# Display.net
KiCad netlist of a schematic drawn in Altium Designer
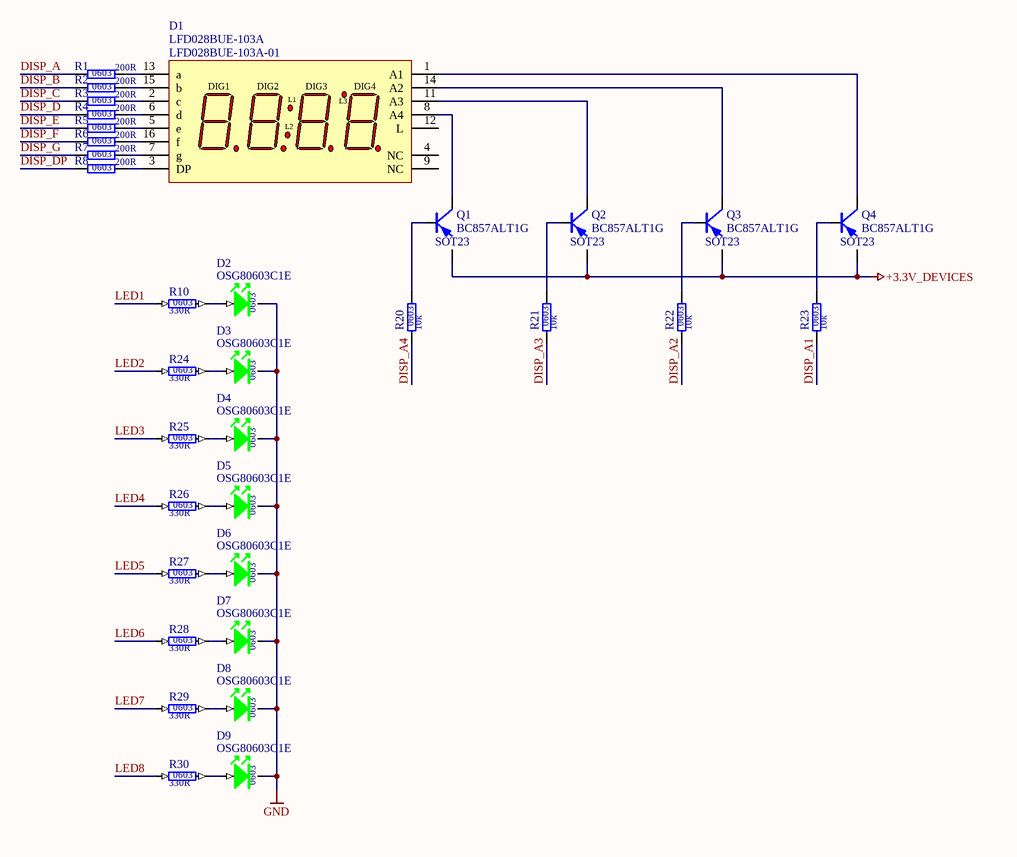
[diagram p0: Display.SchDoc]

(export (version "E")
  (design (tool "Eeschema 10.0.6"))
  (components
    (comp (ref "D1")
      (value "LFD028BUE-103A-01")
      (footprint "LFD028BUE-103A-01")
      (fields
        (field (name "SCH_FOOTPRINT") "LFD028BUE-103A")
        (field (name "PART NUMBER") "OL_LFD028BUE-103A-01")
        (field (name "MANUFACTURER") "WENRUN")
        (field (name "Comment") "4x7 SEG 0.28'")
      )
      (libsource (lib "Library") (part "OL_LFD028BUE-103A"))
    )
    (comp (ref "D2")
      (value "OSG80603C1E")
      (footprint "OL_0603_1608")
      (description "LED GREEN")
      (fields
        (field (name "SCH_FOOTPRINT") "0603")
        (field (name "PART NUMBER") "OL_G_0603_OSG80603C1E")
        (field (name "MANUFACTURER") "Optosupply")
      )
      (libsource (lib "Library") (part "OL_G"))
    )
    (comp (ref "D3")
      (value "OSG80603C1E")
      (footprint "OL_0603_1608")
      (description "LED GREEN")
      (fields
        (field (name "SCH_FOOTPRINT") "0603")
        (field (name "PART NUMBER") "OL_G_0603_OSG80603C1E")
        (field (name "MANUFACTURER") "Optosupply")
      )
      (libsource (lib "Library") (part "OL_G"))
    )
    (comp (ref "D4")
      (value "OSG80603C1E")
      (footprint "OL_0603_1608")
      (description "LED GREEN")
      (fields
        (field (name "SCH_FOOTPRINT") "0603")
        (field (name "PART NUMBER") "OL_G_0603_OSG80603C1E")
        (field (name "MANUFACTURER") "Optosupply")
      )
      (libsource (lib "Library") (part "OL_G"))
    )
    (comp (ref "D5")
      (value "OSG80603C1E")
      (footprint "OL_0603_1608")
      (description "LED GREEN")
      (fields
        (field (name "SCH_FOOTPRINT") "0603")
        (field (name "PART NUMBER") "OL_G_0603_OSG80603C1E")
        (field (name "MANUFACTURER") "Optosupply")
      )
      (libsource (lib "Library") (part "OL_G"))
    )
    (comp (ref "D6")
      (value "OSG80603C1E")
      (footprint "OL_0603_1608")
      (description "LED GREEN")
      (fields
        (field (name "SCH_FOOTPRINT") "0603")
        (field (name "PART NUMBER") "OL_G_0603_OSG80603C1E")
        (field (name "MANUFACTURER") "Optosupply")
      )
      (libsource (lib "Library") (part "OL_G"))
    )
    (comp (ref "D7")
      (value "OSG80603C1E")
      (footprint "OL_0603_1608")
      (description "LED GREEN")
      (fields
        (field (name "SCH_FOOTPRINT") "0603")
        (field (name "PART NUMBER") "OL_G_0603_OSG80603C1E")
        (field (name "MANUFACTURER") "Optosupply")
      )
      (libsource (lib "Library") (part "OL_G"))
    )
    (comp (ref "D8")
      (value "OSG80603C1E")
      (footprint "OL_0603_1608")
      (description "LED GREEN")
      (fields
        (field (name "SCH_FOOTPRINT") "0603")
        (field (name "PART NUMBER") "OL_G_0603_OSG80603C1E")
        (field (name "MANUFACTURER") "Optosupply")
      )
      (libsource (lib "Library") (part "OL_G"))
    )
    (comp (ref "D9")
      (value "OSG80603C1E")
      (footprint "OL_0603_1608")
      (description "LED GREEN")
      (fields
        (field (name "SCH_FOOTPRINT") "0603")
        (field (name "PART NUMBER") "OL_G_0603_OSG80603C1E")
        (field (name "MANUFACTURER") "Optosupply")
      )
      (libsource (lib "Library") (part "OL_G"))
    )
    (comp (ref "Q1")
      (value "BC857ALT1G")
      (footprint "SOT23_TO236_SC59")
      (description "Transitor PNP")
      (fields
        (field (name "SCH_FOOTPRINT") "SOT23")
        (field (name "PART NUMBER") "QPN_BC857ALT1G")
        (field (name "VOLTAGE") "45V")
      )
      (libsource (lib "Library") (part "QPN_BEC"))
    )
    (comp (ref "Q2")
      (value "BC857ALT1G")
      (footprint "SOT23_TO236_SC59")
      (description "Transitor PNP")
      (fields
        (field (name "SCH_FOOTPRINT") "SOT23")
        (field (name "PART NUMBER") "QPN_BC857ALT1G")
        (field (name "VOLTAGE") "45V")
      )
      (libsource (lib "Library") (part "QPN_BEC"))
    )
    (comp (ref "Q3")
      (value "BC857ALT1G")
      (footprint "SOT23_TO236_SC59")
      (description "Transitor PNP")
      (fields
        (field (name "SCH_FOOTPRINT") "SOT23")
        (field (name "PART NUMBER") "QPN_BC857ALT1G")
        (field (name "VOLTAGE") "45V")
      )
      (libsource (lib "Library") (part "QPN_BEC"))
    )
    (comp (ref "Q4")
      (value "BC857ALT1G")
      (footprint "SOT23_TO236_SC59")
      (description "Transitor PNP")
      (fields
        (field (name "SCH_FOOTPRINT") "SOT23")
        (field (name "PART NUMBER") "QPN_BC857ALT1G")
        (field (name "VOLTAGE") "45V")
      )
      (libsource (lib "Library") (part "QPN_BEC"))
    )
    (comp (ref "R1")
      (value "200R")
      (footprint "R_0603_1608")
      (fields
        (field (name "SCH_FOOTPRINT") "0603")
        (field (name "PART NUMBER") "R_200R_0603_1")
        (field (name "VOLTAGE") "50V")
        (field (name "POWER") "100mW")
      )
      (libsource (lib "") (part "R_1"))
    )
    (comp (ref "R2")
      (value "200R")
      (footprint "R_0603_1608")
      (fields
        (field (name "SCH_FOOTPRINT") "0603")
        (field (name "PART NUMBER") "R_200R_0603_1")
        (field (name "VOLTAGE") "50V")
        (field (name "POWER") "100mW")
      )
      (libsource (lib "") (part "R_1"))
    )
    (comp (ref "R3")
      (value "200R")
      (footprint "R_0603_1608")
      (fields
        (field (name "SCH_FOOTPRINT") "0603")
        (field (name "PART NUMBER") "R_200R_0603_1")
        (field (name "VOLTAGE") "50V")
        (field (name "POWER") "100mW")
      )
      (libsource (lib "") (part "R_1"))
    )
    (comp (ref "R4")
      (value "200R")
      (footprint "R_0603_1608")
      (fields
        (field (name "SCH_FOOTPRINT") "0603")
        (field (name "PART NUMBER") "R_200R_0603_1")
        (field (name "VOLTAGE") "50V")
        (field (name "POWER") "100mW")
      )
      (libsource (lib "") (part "R_1"))
    )
    (comp (ref "R5")
      (value "200R")
      (footprint "R_0603_1608")
      (fields
        (field (name "SCH_FOOTPRINT") "0603")
        (field (name "PART NUMBER") "R_200R_0603_1")
        (field (name "VOLTAGE") "50V")
        (field (name "POWER") "100mW")
      )
      (libsource (lib "") (part "R_1"))
    )
    (comp (ref "R6")
      (value "200R")
      (footprint "R_0603_1608")
      (fields
        (field (name "SCH_FOOTPRINT") "0603")
        (field (name "PART NUMBER") "R_200R_0603_1")
        (field (name "VOLTAGE") "50V")
        (field (name "POWER") "100mW")
      )
      (libsource (lib "") (part "R_1"))
    )
    (comp (ref "R7")
      (value "200R")
      (footprint "R_0603_1608")
      (fields
        (field (name "SCH_FOOTPRINT") "0603")
        (field (name "PART NUMBER") "R_200R_0603_1")
        (field (name "VOLTAGE") "50V")
        (field (name "POWER") "100mW")
      )
      (libsource (lib "") (part "R_1"))
    )
    (comp (ref "R8")
      (value "200R")
      (footprint "R_0603_1608")
      (fields
        (field (name "SCH_FOOTPRINT") "0603")
        (field (name "PART NUMBER") "R_200R_0603_1")
        (field (name "VOLTAGE") "50V")
        (field (name "POWER") "100mW")
      )
      (libsource (lib "") (part "R_1"))
    )
    (comp (ref "R10")
      (value "330R")
      (footprint "R_0603_1608")
      (fields
        (field (name "SCH_FOOTPRINT") "0603")
        (field (name "PART NUMBER") "R_330R_0603_1")
        (field (name "VOLTAGE") "50V")
        (field (name "POWER") "100mW")
      )
      (libsource (lib "Library") (part "R"))
    )
    (comp (ref "R20")
      (value "10k")
      (footprint "R_0603_1608")
      (fields
        (field (name "SCH_FOOTPRINT") "0603")
        (field (name "PART NUMBER") "R_10k_0603_1")
        (field (name "VOLTAGE") "75V")
        (field (name "POWER") "100mW")
      )
      (libsource (lib "") (part "R_1"))
    )
    (comp (ref "R21")
      (value "10k")
      (footprint "R_0603_1608")
      (fields
        (field (name "SCH_FOOTPRINT") "0603")
        (field (name "PART NUMBER") "R_10k_0603_1")
        (field (name "VOLTAGE") "75V")
        (field (name "POWER") "100mW")
      )
      (libsource (lib "") (part "R_1"))
    )
    (comp (ref "R22")
      (value "10k")
      (footprint "R_0603_1608")
      (fields
        (field (name "SCH_FOOTPRINT") "0603")
        (field (name "PART NUMBER") "R_10k_0603_1")
        (field (name "VOLTAGE") "75V")
        (field (name "POWER") "100mW")
      )
      (libsource (lib "") (part "R_1"))
    )
    (comp (ref "R23")
      (value "10k")
      (footprint "R_0603_1608")
      (fields
        (field (name "SCH_FOOTPRINT") "0603")
        (field (name "PART NUMBER") "R_10k_0603_1")
        (field (name "VOLTAGE") "75V")
        (field (name "POWER") "100mW")
      )
      (libsource (lib "") (part "R_1"))
    )
    (comp (ref "R24")
      (value "330R")
      (footprint "R_0603_1608")
      (fields
        (field (name "SCH_FOOTPRINT") "0603")
        (field (name "PART NUMBER") "R_330R_0603_1")
        (field (name "VOLTAGE") "50V")
        (field (name "POWER") "100mW")
      )
      (libsource (lib "Library") (part "R"))
    )
    (comp (ref "R25")
      (value "330R")
      (footprint "R_0603_1608")
      (fields
        (field (name "SCH_FOOTPRINT") "0603")
        (field (name "PART NUMBER") "R_330R_0603_1")
        (field (name "VOLTAGE") "50V")
        (field (name "POWER") "100mW")
      )
      (libsource (lib "Library") (part "R"))
    )
    (comp (ref "R26")
      (value "330R")
      (footprint "R_0603_1608")
      (fields
        (field (name "SCH_FOOTPRINT") "0603")
        (field (name "PART NUMBER") "R_330R_0603_1")
        (field (name "VOLTAGE") "50V")
        (field (name "POWER") "100mW")
      )
      (libsource (lib "Library") (part "R"))
    )
    (comp (ref "R27")
      (value "330R")
      (footprint "R_0603_1608")
      (fields
        (field (name "SCH_FOOTPRINT") "0603")
        (field (name "PART NUMBER") "R_330R_0603_1")
        (field (name "VOLTAGE") "50V")
        (field (name "POWER") "100mW")
      )
      (libsource (lib "Library") (part "R"))
    )
    (comp (ref "R28")
      (value "330R")
      (footprint "R_0603_1608")
      (fields
        (field (name "SCH_FOOTPRINT") "0603")
        (field (name "PART NUMBER") "R_330R_0603_1")
        (field (name "VOLTAGE") "50V")
        (field (name "POWER") "100mW")
      )
      (libsource (lib "Library") (part "R"))
    )
    (comp (ref "R29")
      (value "330R")
      (footprint "R_0603_1608")
      (fields
        (field (name "SCH_FOOTPRINT") "0603")
        (field (name "PART NUMBER") "R_330R_0603_1")
        (field (name "VOLTAGE") "50V")
        (field (name "POWER") "100mW")
      )
      (libsource (lib "Library") (part "R"))
    )
    (comp (ref "R30")
      (value "330R")
      (footprint "R_0603_1608")
      (fields
        (field (name "SCH_FOOTPRINT") "0603")
        (field (name "PART NUMBER") "R_330R_0603_1")
        (field (name "VOLTAGE") "50V")
        (field (name "POWER") "100mW")
      )
      (libsource (lib "Library") (part "R"))
    )
  )
  (nets
    (net (code "1") (name "+3.3V_DEVICES") (class "Default")
      (node (ref "Q1") (pin "2") (pinfunction "E_2") (pintype "passive"))
      (node (ref "Q2") (pin "2") (pinfunction "E_2") (pintype "passive"))
      (node (ref "Q3") (pin "2") (pinfunction "E_2") (pintype "passive"))
      (node (ref "Q4") (pin "2") (pinfunction "E_2") (pintype "passive"))
    )
    (net (code "2") (name "/DISP_A") (class "Default")
      (node (ref "R1") (pin "1") (pinfunction "1_1") (pintype "passive"))
    )
    (net (code "3") (name "/DISP_A1") (class "Default")
      (node (ref "R23") (pin "1") (pinfunction "1_1") (pintype "passive"))
    )
    (net (code "4") (name "/DISP_A2") (class "Default")
      (node (ref "R22") (pin "1") (pinfunction "1_1") (pintype "passive"))
    )
    (net (code "5") (name "/DISP_A3") (class "Default")
      (node (ref "R21") (pin "1") (pinfunction "1_1") (pintype "passive"))
    )
    (net (code "6") (name "/DISP_A4") (class "Default")
      (node (ref "R20") (pin "1") (pinfunction "1_1") (pintype "passive"))
    )
    (net (code "7") (name "/DISP_B") (class "Default")
      (node (ref "R2") (pin "1") (pinfunction "1_1") (pintype "passive"))
    )
    (net (code "8") (name "/DISP_C") (class "Default")
      (node (ref "R3") (pin "1") (pinfunction "1_1") (pintype "passive"))
    )
    (net (code "9") (name "/DISP_D") (class "Default")
      (node (ref "R4") (pin "1") (pinfunction "1_1") (pintype "passive"))
    )
    (net (code "10") (name "/DISP_DP") (class "Default")
      (node (ref "R8") (pin "1") (pinfunction "1_1") (pintype "passive"))
    )
    (net (code "11") (name "/DISP_E") (class "Default")
      (node (ref "R5") (pin "1") (pinfunction "1_1") (pintype "passive"))
    )
    (net (code "12") (name "/DISP_F") (class "Default")
      (node (ref "R6") (pin "1") (pinfunction "1_1") (pintype "passive"))
    )
    (net (code "13") (name "/DISP_G") (class "Default")
      (node (ref "R7") (pin "1") (pinfunction "1_1") (pintype "passive"))
    )
    (net (code "14") (name "/LED1") (class "Default")
      (node (ref "R10") (pin "1") (pinfunction "1_1") (pintype "input"))
    )
    (net (code "15") (name "/LED2") (class "Default")
      (node (ref "R24") (pin "1") (pinfunction "1_1") (pintype "input"))
    )
    (net (code "16") (name "/LED3") (class "Default")
      (node (ref "R25") (pin "1") (pinfunction "1_1") (pintype "input"))
    )
    (net (code "17") (name "/LED4") (class "Default")
      (node (ref "R26") (pin "1") (pinfunction "1_1") (pintype "input"))
    )
    (net (code "18") (name "/LED5") (class "Default")
      (node (ref "R27") (pin "1") (pinfunction "1_1") (pintype "input"))
    )
    (net (code "19") (name "/LED6") (class "Default")
      (node (ref "R28") (pin "1") (pinfunction "1_1") (pintype "input"))
    )
    (net (code "20") (name "/LED7") (class "Default")
      (node (ref "R29") (pin "1") (pinfunction "1_1") (pintype "input"))
    )
    (net (code "21") (name "/LED8") (class "Default")
      (node (ref "R30") (pin "1") (pinfunction "1_1") (pintype "input"))
    )
    (net (code "22") (name "GND") (class "Default")
      (node (ref "D2") (pin "1") (pinfunction "K_1") (pintype "output"))
      (node (ref "D3") (pin "1") (pinfunction "K_1") (pintype "output"))
      (node (ref "D4") (pin "1") (pinfunction "K_1") (pintype "output"))
      (node (ref "D5") (pin "1") (pinfunction "K_1") (pintype "output"))
      (node (ref "D6") (pin "1") (pinfunction "K_1") (pintype "output"))
      (node (ref "D7") (pin "1") (pinfunction "K_1") (pintype "output"))
      (node (ref "D8") (pin "1") (pinfunction "K_1") (pintype "output"))
      (node (ref "D9") (pin "1") (pinfunction "K_1") (pintype "output"))
    )
    (net (code "23") (name "Net-(D1-A1)") (class "Default")
      (node (ref "D1") (pin "1") (pinfunction "A1_1") (pintype "passive"))
      (node (ref "Q4") (pin "3") (pinfunction "C_3") (pintype "passive"))
    )
    (net (code "24") (name "Net-(D1-A2)") (class "Default")
      (node (ref "D1") (pin "14") (pinfunction "A2_14") (pintype "passive"))
      (node (ref "Q3") (pin "3") (pinfunction "C_3") (pintype "passive"))
    )
    (net (code "25") (name "Net-(D1-A3)") (class "Default")
      (node (ref "D1") (pin "11") (pinfunction "A3_11") (pintype "passive"))
      (node (ref "Q2") (pin "3") (pinfunction "C_3") (pintype "passive"))
    )
    (net (code "26") (name "Net-(D1-A4)") (class "Default")
      (node (ref "D1") (pin "8") (pinfunction "A4_8") (pintype "passive"))
      (node (ref "Q1") (pin "3") (pinfunction "C_3") (pintype "passive"))
    )
    (net (code "27") (name "Net-(D1-DP)") (class "Default")
      (node (ref "D1") (pin "3") (pinfunction "DP_3") (pintype "passive"))
      (node (ref "R8") (pin "2") (pinfunction "2_2") (pintype "passive"))
    )
    (net (code "28") (name "Net-(D1-a)") (class "Default")
      (node (ref "D1") (pin "13") (pinfunction "a_13") (pintype "passive"))
      (node (ref "R1") (pin "2") (pinfunction "2_2") (pintype "passive"))
    )
    (net (code "29") (name "Net-(D1-b)") (class "Default")
      (node (ref "D1") (pin "15") (pinfunction "b_15") (pintype "passive"))
      (node (ref "R2") (pin "2") (pinfunction "2_2") (pintype "passive"))
    )
    (net (code "30") (name "Net-(D1-c)") (class "Default")
      (node (ref "D1") (pin "2") (pinfunction "c_2") (pintype "passive"))
      (node (ref "R3") (pin "2") (pinfunction "2_2") (pintype "passive"))
    )
    (net (code "31") (name "Net-(D1-d)") (class "Default")
      (node (ref "D1") (pin "6") (pinfunction "d_6") (pintype "passive"))
      (node (ref "R4") (pin "2") (pinfunction "2_2") (pintype "passive"))
    )
    (net (code "32") (name "Net-(D1-e)") (class "Default")
      (node (ref "D1") (pin "5") (pinfunction "e_5") (pintype "passive"))
      (node (ref "R5") (pin "2") (pinfunction "2_2") (pintype "passive"))
    )
    (net (code "33") (name "Net-(D1-f)") (class "Default")
      (node (ref "D1") (pin "16") (pinfunction "f_16") (pintype "passive"))
      (node (ref "R6") (pin "2") (pinfunction "2_2") (pintype "passive"))
    )
    (net (code "34") (name "Net-(D1-g)") (class "Default")
      (node (ref "D1") (pin "7") (pinfunction "g_7") (pintype "passive"))
      (node (ref "R7") (pin "2") (pinfunction "2_2") (pintype "passive"))
    )
    (net (code "35") (name "Net-(D2-A)") (class "Default")
      (node (ref "D2") (pin "2") (pinfunction "A_2") (pintype "input"))
      (node (ref "R10") (pin "2") (pinfunction "2_2") (pintype "output"))
    )
    (net (code "36") (name "Net-(D3-A)") (class "Default")
      (node (ref "D3") (pin "2") (pinfunction "A_2") (pintype "input"))
      (node (ref "R24") (pin "2") (pinfunction "2_2") (pintype "output"))
    )
    (net (code "37") (name "Net-(D4-A)") (class "Default")
      (node (ref "D4") (pin "2") (pinfunction "A_2") (pintype "input"))
      (node (ref "R25") (pin "2") (pinfunction "2_2") (pintype "output"))
    )
    (net (code "38") (name "Net-(D5-A)") (class "Default")
      (node (ref "D5") (pin "2") (pinfunction "A_2") (pintype "input"))
      (node (ref "R26") (pin "2") (pinfunction "2_2") (pintype "output"))
    )
    (net (code "39") (name "Net-(D6-A)") (class "Default")
      (node (ref "D6") (pin "2") (pinfunction "A_2") (pintype "input"))
      (node (ref "R27") (pin "2") (pinfunction "2_2") (pintype "output"))
    )
    (net (code "40") (name "Net-(D7-A)") (class "Default")
      (node (ref "D7") (pin "2") (pinfunction "A_2") (pintype "input"))
      (node (ref "R28") (pin "2") (pinfunction "2_2") (pintype "output"))
    )
    (net (code "41") (name "Net-(D8-A)") (class "Default")
      (node (ref "D8") (pin "2") (pinfunction "A_2") (pintype "input"))
      (node (ref "R29") (pin "2") (pinfunction "2_2") (pintype "output"))
    )
    (net (code "42") (name "Net-(D9-A)") (class "Default")
      (node (ref "D9") (pin "2") (pinfunction "A_2") (pintype "input"))
      (node (ref "R30") (pin "2") (pinfunction "2_2") (pintype "output"))
    )
    (net (code "43") (name "Net-(Q1-B)") (class "Default")
      (node (ref "Q1") (pin "1") (pinfunction "B_1") (pintype "passive"))
      (node (ref "R20") (pin "2") (pinfunction "2_2") (pintype "passive"))
    )
    (net (code "44") (name "Net-(Q2-B)") (class "Default")
      (node (ref "Q2") (pin "1") (pinfunction "B_1") (pintype "passive"))
      (node (ref "R21") (pin "2") (pinfunction "2_2") (pintype "passive"))
    )
    (net (code "45") (name "Net-(Q3-B)") (class "Default")
      (node (ref "Q3") (pin "1") (pinfunction "B_1") (pintype "passive"))
      (node (ref "R22") (pin "2") (pinfunction "2_2") (pintype "passive"))
    )
    (net (code "46") (name "Net-(Q4-B)") (class "Default")
      (node (ref "Q4") (pin "1") (pinfunction "B_1") (pintype "passive"))
      (node (ref "R23") (pin "2") (pinfunction "2_2") (pintype "passive"))
    )
    (net (code "47") (name "unconnected-(D1-L-Pad12)") (class "Default")
      (node (ref "D1") (pin "12") (pinfunction "L_12") (pintype "passive"))
    )
    (net (code "48") (name "unconnected-(D1-NC-Pad4)") (class "Default")
      (node (ref "D1") (pin "4") (pinfunction "NC_4") (pintype "passive"))
    )
    (net (code "49") (name "unconnected-(D1-NC-Pad9)") (class "Default")
      (node (ref "D1") (pin "9") (pinfunction "NC_9") (pintype "passive"))
    )
  )
)
